# SmartRock_4-pin_EC_Breakout_v5.net
KiCad netlist of a schematic drawn in EAGLE
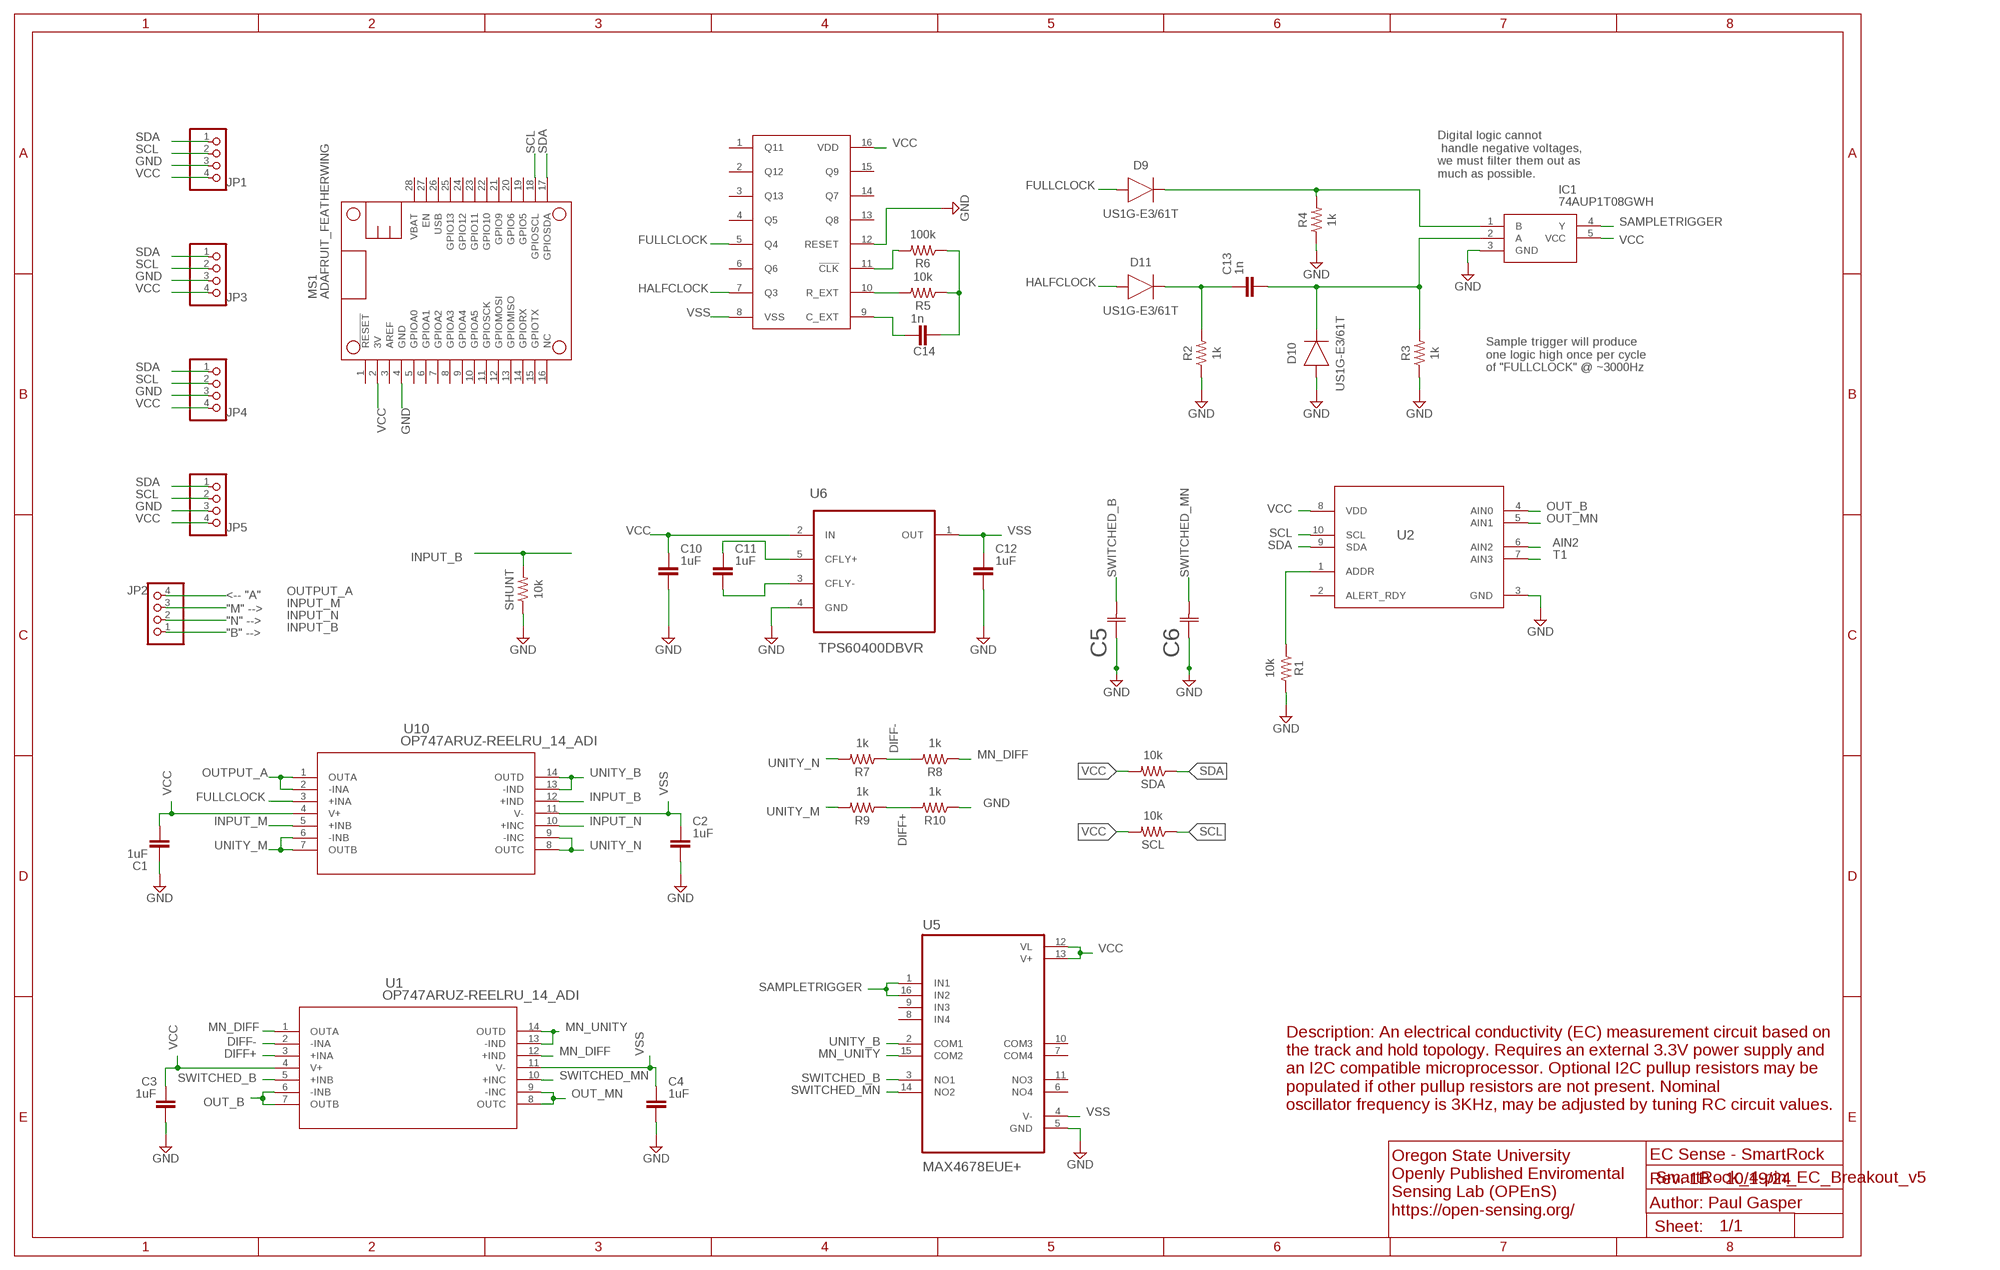
[diagram p0: schematic, sheet 1]

(export (version "E")
  (design (tool "Eeschema 10.0.6"))
  (components
    (comp (ref "C1")
      (value "1uF")
      (footprint "eagle-import:CAPC1005X60")
      (libsource (lib "eagle-import") (part "CCHIP-0402(1005-METRIC)_"))
    )
    (comp (ref "C2")
      (value "1uF")
      (footprint "eagle-import:CAPC1005X60")
      (libsource (lib "eagle-import") (part "CCHIP-0402(1005-METRIC)_"))
    )
    (comp (ref "C3")
      (value "1uF")
      (footprint "eagle-import:CAPC1005X60")
      (libsource (lib "eagle-import") (part "CCHIP-0402(1005-METRIC)_"))
    )
    (comp (ref "C4")
      (value "1uF")
      (footprint "eagle-import:CAPC1005X60")
      (libsource (lib "eagle-import") (part "CCHIP-0402(1005-METRIC)_"))
    )
    (comp (ref "C5")
      (value "865090640004CAP_WCAP-ASLU_04P0X05P5_WRE-L")
      (footprint "eagle-import:CAP_WCAP-ASLU_04P0X05P5_WRE-L")
      (fields
        (field (name "MANUFACTURER_PART_NUMBER") "865090640004")
        (field (name "COPYRIGHT") "Copyright (C) 2024 Ultra Librarian. All rights reserved.")
      )
      (libsource (lib "eagle-import") (part "865090640004CAP_WCAP-ASLU_04P0X05P5_WRE-L"))
    )
    (comp (ref "C6")
      (value "865090640004CAP_WCAP-ASLU_04P0X05P5_WRE-L")
      (footprint "eagle-import:CAP_WCAP-ASLU_04P0X05P5_WRE-L")
      (fields
        (field (name "MANUFACTURER_PART_NUMBER") "865090640004")
        (field (name "COPYRIGHT") "Copyright (C) 2024 Ultra Librarian. All rights reserved.")
      )
      (libsource (lib "eagle-import") (part "865090640004CAP_WCAP-ASLU_04P0X05P5_WRE-L"))
    )
    (comp (ref "C10")
      (value "1uF")
      (footprint "eagle-import:CAPC1005X60")
      (libsource (lib "eagle-import") (part "CCHIP-0402(1005-METRIC)_"))
    )
    (comp (ref "C11")
      (value "1uF")
      (footprint "eagle-import:CAPC1005X60")
      (libsource (lib "eagle-import") (part "CCHIP-0402(1005-METRIC)_"))
    )
    (comp (ref "C12")
      (value "1uF")
      (footprint "eagle-import:CAPC1005X60")
      (libsource (lib "eagle-import") (part "CCHIP-0402(1005-METRIC)_"))
    )
    (comp (ref "C13")
      (value "1n")
      (footprint "eagle-import:CAPC1005X60")
      (libsource (lib "eagle-import") (part "CCHIP-0402(1005-METRIC)_"))
    )
    (comp (ref "C14")
      (value "1n")
      (footprint "eagle-import:CAPC1005X60")
      (libsource (lib "eagle-import") (part "CCHIP-0402(1005-METRIC)_"))
    )
    (comp (ref "D9")
      (value "US1G-E3/61T")
      (footprint "eagle-import:DIOM5226X290N")
      (fields (field (name "MANUFACTURER") "Vishay Semiconductor Diodes Division"))
      (libsource (lib "eagle-import") (part "DIODE__SMAUS1G-E3/61T"))
    )
    (comp (ref "D10")
      (value "US1G-E3/61T")
      (footprint "eagle-import:DIOM5226X290N")
      (fields (field (name "MANUFACTURER") "Vishay Semiconductor Diodes Division"))
      (libsource (lib "eagle-import") (part "DIODE__SMAUS1G-E3/61T"))
    )
    (comp (ref "D11")
      (value "US1G-E3/61T")
      (footprint "eagle-import:DIOM5226X290N")
      (fields (field (name "MANUFACTURER") "Vishay Semiconductor Diodes Division"))
      (libsource (lib "eagle-import") (part "DIODE__SMAUS1G-E3/61T"))
    )
    (comp (ref "IC1")
      (value "74AUP1T08GWH")
      (footprint "eagle-import:SOT65P212X110-5N")
      (fields (field (name "MOUSER_PART_NUMBER") "771-74AUP1T08GWH"))
      (libsource (lib "eagle-import") (part "74AUP1T08GWH"))
    )
    (comp (ref "JP1")
      (value "PINHD-1X4")
      (footprint "eagle-import:1X04")
      (libsource (lib "eagle-import") (part "PINHD-1X4"))
    )
    (comp (ref "JP2")
      (value "PINHD-1X4")
      (footprint "eagle-import:1X04")
      (libsource (lib "eagle-import") (part "PINHD-1X4"))
    )
    (comp (ref "JP3")
      (value "PINHD-1X4")
      (footprint "eagle-import:1X04")
      (libsource (lib "eagle-import") (part "PINHD-1X4"))
    )
    (comp (ref "JP4")
      (value "PINHD-1X4")
      (footprint "eagle-import:1X04")
      (libsource (lib "eagle-import") (part "PINHD-1X4"))
    )
    (comp (ref "JP5")
      (value "PINHD-1X4")
      (footprint "eagle-import:1X04")
      (libsource (lib "eagle-import") (part "PINHD-1X4"))
    )
    (comp (ref "MS1")
      (value "ADAFRUIT_FEATHERWING")
      (footprint "eagle-import:ADAFRUIT_FEATHERWING")
      (libsource (lib "eagle-import") (part "ADAFRUIT_FEATHERWING"))
    )
    (comp (ref "R1")
      (value "10k")
      (footprint "eagle-import:RESC1005X40")
      (libsource (lib "eagle-import") (part "R-USCHIP-0402(1005-METRIC)_"))
    )
    (comp (ref "R2")
      (value "1k")
      (footprint "eagle-import:RESC1005X40")
      (libsource (lib "eagle-import") (part "R-USCHIP-0402(1005-METRIC)_"))
    )
    (comp (ref "R3")
      (value "1k")
      (footprint "eagle-import:RESC1005X40")
      (libsource (lib "eagle-import") (part "R-USCHIP-0402(1005-METRIC)_"))
    )
    (comp (ref "R4")
      (value "1k")
      (footprint "eagle-import:RESC1005X40")
      (libsource (lib "eagle-import") (part "R-USCHIP-0402(1005-METRIC)_"))
    )
    (comp (ref "R5")
      (value "10k")
      (footprint "eagle-import:RESC1005X40")
      (libsource (lib "eagle-import") (part "R-USCHIP-0402(1005-METRIC)_"))
    )
    (comp (ref "R6")
      (value "100k")
      (footprint "eagle-import:RESC1005X40")
      (libsource (lib "eagle-import") (part "R-USCHIP-0402(1005-METRIC)_"))
    )
    (comp (ref "R7")
      (value "1k")
      (footprint "eagle-import:RESC1005X40")
      (libsource (lib "eagle-import") (part "R-USCHIP-0402(1005-METRIC)_"))
    )
    (comp (ref "R8")
      (value "1k")
      (footprint "eagle-import:RESC1005X40")
      (libsource (lib "eagle-import") (part "R-USCHIP-0402(1005-METRIC)_"))
    )
    (comp (ref "R9")
      (value "1k")
      (footprint "eagle-import:RESC1005X40")
      (libsource (lib "eagle-import") (part "R-USCHIP-0402(1005-METRIC)_"))
    )
    (comp (ref "R10")
      (value "1k")
      (footprint "eagle-import:RESC1005X40")
      (libsource (lib "eagle-import") (part "R-USCHIP-0402(1005-METRIC)_"))
    )
    (comp (ref "SCL")
      (value "10k")
      (footprint "eagle-import:RESC1005X40")
      (libsource (lib "eagle-import") (part "R-USCHIP-0402(1005-METRIC)_"))
    )
    (comp (ref "SDA")
      (value "10k")
      (footprint "eagle-import:RESC1005X40")
      (libsource (lib "eagle-import") (part "R-USCHIP-0402(1005-METRIC)_"))
    )
    (comp (ref "SHUNT")
      (value "10k")
      (footprint "eagle-import:RESC1005X40")
      (libsource (lib "eagle-import") (part "R-USCHIP-0402(1005-METRIC)_"))
    )
    (comp (ref "U1")
      (value "OP747ARUZ-REELRU_14_ADI")
      (footprint "eagle-import:RU_14_ADI")
      (fields
        (field (name "MANUFACTURER_PART_NUMBER") "OP747ARUZ-REEL")
        (field (name "COPYRIGHT") "Copyright (C) 2024 Ultra Librarian. All rights reserved.")
      )
      (libsource (lib "eagle-import") (part "OP747ARUZ-REELRU_14_ADI"))
    )
    (comp (ref "U2")
      (value "ADS1115IDGSRDGS0010A_L")
      (footprint "eagle-import:DGS0010A_L")
      (fields
        (field (name "MANUFACTURER_PART_NUMBER") "ADS1115IDGSR")
        (field (name "COPYRIGHT") "Copyright (C) 2024 Ultra Librarian. All rights reserved.")
      )
      (libsource (lib "eagle-import") (part "ADS1115IDGSRDGS0010A_L"))
    )
    (comp (ref "U4")
      (value "CD4060BPWR")
      (footprint "eagle-import:CD4060BPWR")
      (libsource (lib "eagle-import") (part "CD4060BPWR"))
    )
    (comp (ref "U5")
      (value "MAX4678EUE+")
      (footprint "eagle-import:SOP65P640X110-16N")
      (libsource (lib "eagle-import") (part "MAX4678EUE+"))
    )
    (comp (ref "U6")
      (value "TPS60400DBVR")
      (footprint "eagle-import:SOT95P280X145-5N")
      (fields (field (name "MF") "Texas Instruments"))
      (libsource (lib "eagle-import") (part "TPS60400DBVR"))
    )
    (comp (ref "U10")
      (value "OP747ARUZ-REELRU_14_ADI")
      (footprint "eagle-import:RU_14_ADI")
      (fields
        (field (name "MANUFACTURER_PART_NUMBER") "OP747ARUZ-REEL")
        (field (name "COPYRIGHT") "Copyright (C) 2024 Ultra Librarian. All rights reserved.")
      )
      (libsource (lib "eagle-import") (part "OP747ARUZ-REELRU_14_ADI"))
    )
  )
  (nets
    (net (code "1") (name "/AIN2") (class "Default")
      (node (ref "U2") (pin "6") (pinfunction "AIN2_6") (pintype "input"))
    )
    (net (code "2") (name "/DIFF+") (class "Default")
      (node (ref "R10") (pin "2") (pinfunction "2_2") (pintype "passive"))
      (node (ref "R9") (pin "1") (pinfunction "1_1") (pintype "passive"))
      (node (ref "U1") (pin "3") (pinfunction "+INA_3") (pintype "passive"))
    )
    (net (code "3") (name "/DIFF-") (class "Default")
      (node (ref "R7") (pin "1") (pinfunction "1_1") (pintype "passive"))
      (node (ref "R8") (pin "2") (pinfunction "2_2") (pintype "passive"))
      (node (ref "U1") (pin "2") (pinfunction "-INA_2") (pintype "passive"))
    )
    (net (code "4") (name "/FULLCLOCK") (class "Default")
      (node (ref "D9") (pin "2") (pinfunction "A_2") (pintype "passive"))
      (node (ref "U10") (pin "3") (pinfunction "+INA_3") (pintype "passive"))
      (node (ref "U4") (pin "5") (pinfunction "Q4_5") (pintype "bidirectional"))
    )
    (net (code "5") (name "/HALFCLOCK") (class "Default")
      (node (ref "D11") (pin "2") (pinfunction "A_2") (pintype "passive"))
      (node (ref "U4") (pin "7") (pinfunction "Q3_7") (pintype "bidirectional"))
    )
    (net (code "6") (name "/INPUT_B") (class "Default")
      (node (ref "JP2") (pin "1") (pinfunction "1_1") (pintype "passive"))
      (node (ref "SHUNT") (pin "2") (pinfunction "2_2") (pintype "passive"))
      (node (ref "U10") (pin "12") (pinfunction "+IND_12") (pintype "passive"))
    )
    (net (code "7") (name "/INPUT_M") (class "Default")
      (node (ref "JP2") (pin "3") (pinfunction "3_3") (pintype "passive"))
      (node (ref "U10") (pin "5") (pinfunction "+INB_5") (pintype "passive"))
    )
    (net (code "8") (name "/INPUT_N") (class "Default")
      (node (ref "JP2") (pin "2") (pinfunction "2_2") (pintype "passive"))
      (node (ref "U10") (pin "10") (pinfunction "+INC_10") (pintype "passive"))
    )
    (net (code "9") (name "/MN_DIFF") (class "Default")
      (node (ref "R8") (pin "1") (pinfunction "1_1") (pintype "passive"))
      (node (ref "U1") (pin "1") (pinfunction "OUTA_1") (pintype "passive"))
      (node (ref "U1") (pin "12") (pinfunction "+IND_12") (pintype "passive"))
    )
    (net (code "10") (name "/MN_UNITY") (class "Default")
      (node (ref "U1") (pin "13") (pinfunction "-IND_13") (pintype "passive"))
      (node (ref "U1") (pin "14") (pinfunction "OUTD_14") (pintype "passive"))
      (node (ref "U5") (pin "15") (pinfunction "COM2_15") (pintype "bidirectional"))
    )
    (net (code "11") (name "/OUTPUT_A") (class "Default")
      (node (ref "JP2") (pin "4") (pinfunction "4_4") (pintype "passive"))
      (node (ref "U10") (pin "1") (pinfunction "OUTA_1") (pintype "passive"))
      (node (ref "U10") (pin "2") (pinfunction "-INA_2") (pintype "passive"))
    )
    (net (code "12") (name "/OUT_B") (class "Default")
      (node (ref "U1") (pin "6") (pinfunction "-INB_6") (pintype "passive"))
      (node (ref "U1") (pin "7") (pinfunction "OUTB_7") (pintype "passive"))
      (node (ref "U2") (pin "4") (pinfunction "AIN0_4") (pintype "input"))
    )
    (net (code "13") (name "/OUT_MN") (class "Default")
      (node (ref "U1") (pin "8") (pinfunction "OUTC_8") (pintype "passive"))
      (node (ref "U1") (pin "9") (pinfunction "-INC_9") (pintype "passive"))
      (node (ref "U2") (pin "5") (pinfunction "AIN1_5") (pintype "input"))
    )
    (net (code "14") (name "/SAMPLETRIGGER") (class "Default")
      (node (ref "IC1") (pin "4") (pinfunction "Y_4") (pintype "bidirectional"))
      (node (ref "U5") (pin "1") (pinfunction "IN1_1") (pintype "input"))
      (node (ref "U5") (pin "16") (pinfunction "IN2_16") (pintype "input"))
    )
    (net (code "15") (name "/SWITCHED_B") (class "Default")
      (node (ref "C5") (pin "2") (pinfunction "2_2") (pintype "passive"))
      (node (ref "U1") (pin "5") (pinfunction "+INB_5") (pintype "passive"))
      (node (ref "U5") (pin "3") (pinfunction "NO1_3") (pintype "bidirectional"))
    )
    (net (code "16") (name "/SWITCHED_MN") (class "Default")
      (node (ref "C6") (pin "2") (pinfunction "2_2") (pintype "passive"))
      (node (ref "U1") (pin "10") (pinfunction "+INC_10") (pintype "passive"))
      (node (ref "U5") (pin "14") (pinfunction "NO2_14") (pintype "bidirectional"))
    )
    (net (code "17") (name "/T1") (class "Default")
      (node (ref "U2") (pin "7") (pinfunction "AIN3_7") (pintype "input"))
    )
    (net (code "18") (name "/UNITY_B") (class "Default")
      (node (ref "U10") (pin "13") (pinfunction "-IND_13") (pintype "passive"))
      (node (ref "U10") (pin "14") (pinfunction "OUTD_14") (pintype "passive"))
      (node (ref "U5") (pin "2") (pinfunction "COM1_2") (pintype "bidirectional"))
    )
    (net (code "19") (name "/UNITY_M") (class "Default")
      (node (ref "R9") (pin "2") (pinfunction "2_2") (pintype "passive"))
      (node (ref "U10") (pin "6") (pinfunction "-INB_6") (pintype "passive"))
      (node (ref "U10") (pin "7") (pinfunction "OUTB_7") (pintype "passive"))
    )
    (net (code "20") (name "/UNITY_N") (class "Default")
      (node (ref "R7") (pin "2") (pinfunction "2_2") (pintype "passive"))
      (node (ref "U10") (pin "8") (pinfunction "OUTC_8") (pintype "passive"))
      (node (ref "U10") (pin "9") (pinfunction "-INC_9") (pintype "passive"))
    )
    (net (code "21") (name "/USB") (class "Default")
      (node (ref "MS1") (pin "26") (pinfunction "USB_26") (pintype "power_in"))
    )
    (net (code "22") (name "/VBAT") (class "Default")
      (node (ref "MS1") (pin "28") (pinfunction "VBAT_28") (pintype "power_in"))
    )
    (net (code "23") (name "/VSS") (class "Default")
      (node (ref "C12") (pin "1") (pinfunction "1_1") (pintype "passive"))
      (node (ref "C2") (pin "1") (pinfunction "1_1") (pintype "passive"))
      (node (ref "C4") (pin "1") (pinfunction "1_1") (pintype "passive"))
      (node (ref "U1") (pin "11") (pinfunction "V-_11") (pintype "power_in"))
      (node (ref "U10") (pin "11") (pinfunction "V-_11") (pintype "power_in"))
      (node (ref "U4") (pin "8") (pinfunction "VSS_8") (pintype "bidirectional"))
      (node (ref "U5") (pin "4") (pinfunction "V-_4") (pintype "power_in"))
      (node (ref "U6") (pin "1") (pinfunction "OUT_1") (pintype "output"))
    )
    (net (code "24") (name "GND") (class "Default")
      (node (ref "C1") (pin "1") (pinfunction "1_1") (pintype "passive"))
      (node (ref "C10") (pin "2") (pinfunction "2_2") (pintype "passive"))
      (node (ref "C12") (pin "2") (pinfunction "2_2") (pintype "passive"))
      (node (ref "C2") (pin "2") (pinfunction "2_2") (pintype "passive"))
      (node (ref "C3") (pin "2") (pinfunction "2_2") (pintype "passive"))
      (node (ref "C4") (pin "2") (pinfunction "2_2") (pintype "passive"))
      (node (ref "C5") (pin "1") (pinfunction "1_1") (pintype "passive"))
      (node (ref "C6") (pin "1") (pinfunction "1_1") (pintype "passive"))
      (node (ref "D10") (pin "2") (pinfunction "A_2") (pintype "passive"))
      (node (ref "IC1") (pin "3") (pinfunction "GND_3") (pintype "bidirectional"))
      (node (ref "JP1") (pin "3") (pinfunction "3_3") (pintype "passive"))
      (node (ref "JP3") (pin "3") (pinfunction "3_3") (pintype "passive"))
      (node (ref "JP4") (pin "3") (pinfunction "3_3") (pintype "passive"))
      (node (ref "JP5") (pin "3") (pinfunction "3_3") (pintype "passive"))
      (node (ref "MS1") (pin "4") (pinfunction "GND_4") (pintype "power_in"))
      (node (ref "R1") (pin "2") (pinfunction "2_2") (pintype "passive"))
      (node (ref "R10") (pin "1") (pinfunction "1_1") (pintype "passive"))
      (node (ref "R2") (pin "1") (pinfunction "1_1") (pintype "passive"))
      (node (ref "R3") (pin "1") (pinfunction "1_1") (pintype "passive"))
      (node (ref "R4") (pin "1") (pinfunction "1_1") (pintype "passive"))
      (node (ref "SHUNT") (pin "1") (pinfunction "1_1") (pintype "passive"))
      (node (ref "U2") (pin "3") (pinfunction "GND_3") (pintype "power_in"))
      (node (ref "U4") (pin "12") (pinfunction "RESET_12") (pintype "bidirectional"))
      (node (ref "U5") (pin "5") (pinfunction "GND_5") (pintype "power_in"))
      (node (ref "U6") (pin "4") (pinfunction "GND_4") (pintype "passive"))
    )
    (net (code "25") (name "Net-(C14-Pad2)") (class "Default")
      (node (ref "C14") (pin "2") (pinfunction "2_2") (pintype "passive"))
      (node (ref "R5") (pin "1") (pinfunction "1_1") (pintype "passive"))
      (node (ref "R6") (pin "1") (pinfunction "1_1") (pintype "passive"))
    )
    (net (code "26") (name "Net-(D9-C)") (class "Default")
      (node (ref "D9") (pin "1") (pinfunction "C_1") (pintype "passive"))
      (node (ref "IC1") (pin "1") (pinfunction "B_1") (pintype "bidirectional"))
      (node (ref "R4") (pin "2") (pinfunction "2_2") (pintype "passive"))
    )
    (net (code "27") (name "Net-(D10-C)") (class "Default")
      (node (ref "C13") (pin "2") (pinfunction "2_2") (pintype "passive"))
      (node (ref "D10") (pin "1") (pinfunction "C_1") (pintype "passive"))
      (node (ref "IC1") (pin "2") (pinfunction "A_2") (pintype "bidirectional"))
      (node (ref "R3") (pin "2") (pinfunction "2_2") (pintype "passive"))
    )
    (net (code "28") (name "Net-(D11-C)") (class "Default")
      (node (ref "C13") (pin "1") (pinfunction "1_1") (pintype "passive"))
      (node (ref "D11") (pin "1") (pinfunction "C_1") (pintype "passive"))
      (node (ref "R2") (pin "2") (pinfunction "2_2") (pintype "passive"))
    )
    (net (code "29") (name "Net-(U2-ADDR)") (class "Default")
      (node (ref "R1") (pin "1") (pinfunction "1_1") (pintype "passive"))
      (node (ref "U2") (pin "1") (pinfunction "ADDR_1") (pintype "input"))
    )
    (net (code "30") (name "Net-(U4-C_EXT)") (class "Default")
      (node (ref "C14") (pin "1") (pinfunction "1_1") (pintype "passive"))
      (node (ref "U4") (pin "9") (pinfunction "C_EXT_9") (pintype "bidirectional"))
    )
    (net (code "31") (name "Net-(U4-R_EXT)") (class "Default")
      (node (ref "R5") (pin "2") (pinfunction "2_2") (pintype "passive"))
      (node (ref "U4") (pin "10") (pinfunction "R_EXT_10") (pintype "bidirectional"))
    )
    (net (code "32") (name "Net-(U4-~{CLK})") (class "Default")
      (node (ref "R6") (pin "2") (pinfunction "2_2") (pintype "passive"))
      (node (ref "U4") (pin "11") (pinfunction "~{CLK}_11") (pintype "bidirectional"))
    )
    (net (code "33") (name "Net-(U6-CFLY+)") (class "Default")
      (node (ref "C11") (pin "1") (pinfunction "1_1") (pintype "passive"))
      (node (ref "U6") (pin "5") (pinfunction "CFLY+_5") (pintype "input"))
    )
    (net (code "34") (name "Net-(U6-CFLY-)") (class "Default")
      (node (ref "C11") (pin "2") (pinfunction "2_2") (pintype "passive"))
      (node (ref "U6") (pin "3") (pinfunction "CFLY-_3") (pintype "input"))
    )
    (net (code "35") (name "SCL") (class "Default")
      (node (ref "JP1") (pin "2") (pinfunction "2_2") (pintype "passive"))
      (node (ref "JP3") (pin "2") (pinfunction "2_2") (pintype "passive"))
      (node (ref "JP4") (pin "2") (pinfunction "2_2") (pintype "passive"))
      (node (ref "JP5") (pin "2") (pinfunction "2_2") (pintype "passive"))
      (node (ref "MS1") (pin "18") (pinfunction "GPIOSCL_18") (pintype "bidirectional"))
      (node (ref "SCL") (pin "1") (pinfunction "1_1") (pintype "passive"))
      (node (ref "U2") (pin "10") (pinfunction "SCL_10") (pintype "input"))
    )
    (net (code "36") (name "SDA") (class "Default")
      (node (ref "JP1") (pin "1") (pinfunction "1_1") (pintype "passive"))
      (node (ref "JP3") (pin "1") (pinfunction "1_1") (pintype "passive"))
      (node (ref "JP4") (pin "1") (pinfunction "1_1") (pintype "passive"))
      (node (ref "JP5") (pin "1") (pinfunction "1_1") (pintype "passive"))
      (node (ref "MS1") (pin "17") (pinfunction "GPIOSDA_17") (pintype "bidirectional"))
      (node (ref "SDA") (pin "1") (pinfunction "1_1") (pintype "passive"))
      (node (ref "U2") (pin "9") (pinfunction "SDA_9") (pintype "bidirectional"))
    )
    (net (code "37") (name "VCC") (class "Default")
      (node (ref "C1") (pin "2") (pinfunction "2_2") (pintype "passive"))
      (node (ref "C10") (pin "1") (pinfunction "1_1") (pintype "passive"))
      (node (ref "C3") (pin "1") (pinfunction "1_1") (pintype "passive"))
      (node (ref "IC1") (pin "5") (pinfunction "VCC_5") (pintype "bidirectional"))
      (node (ref "JP1") (pin "4") (pinfunction "4_4") (pintype "passive"))
      (node (ref "JP3") (pin "4") (pinfunction "4_4") (pintype "passive"))
      (node (ref "JP4") (pin "4") (pinfunction "4_4") (pintype "passive"))
      (node (ref "JP5") (pin "4") (pinfunction "4_4") (pintype "passive"))
      (node (ref "MS1") (pin "2") (pinfunction "3V_2") (pintype "power_in"))
      (node (ref "SCL") (pin "2") (pinfunction "2_2") (pintype "passive"))
      (node (ref "SDA") (pin "2") (pinfunction "2_2") (pintype "passive"))
      (node (ref "U1") (pin "4") (pinfunction "V+_4") (pintype "power_in"))
      (node (ref "U10") (pin "4") (pinfunction "V+_4") (pintype "power_in"))
      (node (ref "U2") (pin "8") (pinfunction "VDD_8") (pintype "power_in"))
      (node (ref "U4") (pin "16") (pinfunction "VDD_16") (pintype "bidirectional"))
      (node (ref "U5") (pin "12") (pinfunction "VL_12") (pintype "power_in"))
      (node (ref "U5") (pin "13") (pinfunction "V+_13") (pintype "power_in"))
      (node (ref "U6") (pin "2") (pinfunction "IN_2") (pintype "power_in"))
    )
    (net (code "38") (name "unconnected-(MS1-AREF-Pad3)") (class "Default")
      (node (ref "MS1") (pin "3") (pinfunction "AREF_3") (pintype "passive"))
    )
    (net (code "39") (name "unconnected-(MS1-EN-Pad27)") (class "Default")
      (node (ref "MS1") (pin "27") (pinfunction "EN_27") (pintype "passive"))
    )
    (net (code "40") (name "unconnected-(MS1-GPIO5-Pad19)") (class "Default")
      (node (ref "MS1") (pin "19") (pinfunction "GPIO5_19") (pintype "bidirectional"))
    )
    (net (code "41") (name "unconnected-(MS1-GPIO6-Pad20)") (class "Default")
      (node (ref "MS1") (pin "20") (pinfunction "GPIO6_20") (pintype "bidirectional"))
    )
    (net (code "42") (name "unconnected-(MS1-GPIO9-Pad21)") (class "Default")
      (node (ref "MS1") (pin "21") (pinfunction "GPIO9_21") (pintype "bidirectional"))
    )
    (net (code "43") (name "unconnected-(MS1-GPIO10-Pad22)") (class "Default")
      (node (ref "MS1") (pin "22") (pinfunction "GPIO10_22") (pintype "bidirectional"))
    )
    (net (code "44") (name "unconnected-(MS1-GPIO11-Pad23)") (class "Default")
      (node (ref "MS1") (pin "23") (pinfunction "GPIO11_23") (pintype "bidirectional"))
    )
    (net (code "45") (name "unconnected-(MS1-GPIO12-Pad24)") (class "Default")
      (node (ref "MS1") (pin "24") (pinfunction "GPIO12_24") (pintype "bidirectional"))
    )
    (net (code "46") (name "unconnected-(MS1-GPIO13-Pad25)") (class "Default")
      (node (ref "MS1") (pin "25") (pinfunction "GPIO13_25") (pintype "bidirectional"))
    )
    (net (code "47") (name "unconnected-(MS1-GPIOA0-Pad5)") (class "Default")
      (node (ref "MS1") (pin "5") (pinfunction "GPIOA0_5") (pintype "bidirectional"))
    )
    (net (code "48") (name "unconnected-(MS1-GPIOA1-Pad6)") (class "Default")
      (node (ref "MS1") (pin "6") (pinfunction "GPIOA1_6") (pintype "bidirectional"))
    )
    (net (code "49") (name "unconnected-(MS1-GPIOA2-Pad7)") (class "Default")
      (node (ref "MS1") (pin "7") (pinfunction "GPIOA2_7") (pintype "bidirectional"))
    )
    (net (code "50") (name "unconnected-(MS1-GPIOA3-Pad8)") (class "Default")
      (node (ref "MS1") (pin "8") (pinfunction "GPIOA3_8") (pintype "bidirectional"))
    )
    (net (code "51") (name "unconnected-(MS1-GPIOA4-Pad9)") (class "Default")
      (node (ref "MS1") (pin "9") (pinfunction "GPIOA4_9") (pintype "bidirectional"))
    )
    (net (code "52") (name "unconnected-(MS1-GPIOA5-Pad10)") (class "Default")
      (node (ref "MS1") (pin "10") (pinfunction "GPIOA5_10") (pintype "bidirectional"))
    )
    (net (code "53") (name "unconnected-(MS1-GPIOMISO-Pad13)") (class "Default")
      (node (ref "MS1") (pin "13") (pinfunction "GPIOMISO_13") (pintype "bidirectional"))
    )
    (net (code "54") (name "unconnected-(MS1-GPIOMOSI-Pad12)") (class "Default")
      (node (ref "MS1") (pin "12") (pinfunction "GPIOMOSI_12") (pintype "bidirectional"))
    )
    (net (code "55") (name "unconnected-(MS1-GPIORX-Pad14)") (class "Default")
      (node (ref "MS1") (pin "14") (pinfunction "GPIORX_14") (pintype "bidirectional"))
    )
    (net (code "56") (name "unconnected-(MS1-GPIOSCK-Pad11)") (class "Default")
      (node (ref "MS1") (pin "11") (pinfunction "GPIOSCK_11") (pintype "bidirectional"))
    )
    (net (code "57") (name "unconnected-(MS1-GPIOTX-Pad15)") (class "Default")
      (node (ref "MS1") (pin "15") (pinfunction "GPIOTX_15") (pintype "bidirectional"))
    )
    (net (code "58") (name "unconnected-(MS1-NC-Pad16)") (class "Default")
      (node (ref "MS1") (pin "16") (pinfunction "NC_16") (pintype "passive"))
    )
    (net (code "59") (name "unconnected-(MS1-~{RESET}-Pad1)") (class "Default")
      (node (ref "MS1") (pin "1") (pinfunction "~{RESET}_1") (pintype "input"))
    )
    (net (code "60") (name "unconnected-(U2-ALERT_RDY-Pad2)") (class "Default")
      (node (ref "U2") (pin "2") (pinfunction "ALERT_RDY_2") (pintype "output"))
    )
    (net (code "61") (name "unconnected-(U4-Q5-Pad4)") (class "Default")
      (node (ref "U4") (pin "4") (pinfunction "Q5_4") (pintype "bidirectional"))
    )
    (net (code "62") (name "unconnected-(U4-Q6-Pad6)") (class "Default")
      (node (ref "U4") (pin "6") (pinfunction "Q6_6") (pintype "bidirectional"))
    )
    (net (code "63") (name "unconnected-(U4-Q7-Pad14)") (class "Default")
      (node (ref "U4") (pin "14") (pinfunction "Q7_14") (pintype "bidirectional"))
    )
    (net (code "64") (name "unconnected-(U4-Q8-Pad13)") (class "Default")
      (node (ref "U4") (pin "13") (pinfunction "Q8_13") (pintype "bidirectional"))
    )
    (net (code "65") (name "unconnected-(U4-Q9-Pad15)") (class "Default")
      (node (ref "U4") (pin "15") (pinfunction "Q9_15") (pintype "bidirectional"))
    )
    (net (code "66") (name "unconnected-(U4-Q11-Pad1)") (class "Default")
      (node (ref "U4") (pin "1") (pinfunction "Q11_1") (pintype "bidirectional"))
    )
    (net (code "67") (name "unconnected-(U4-Q12-Pad2)") (class "Default")
      (node (ref "U4") (pin "2") (pinfunction "Q12_2") (pintype "bidirectional"))
    )
    (net (code "68") (name "unconnected-(U4-Q13-Pad3)") (class "Default")
      (node (ref "U4") (pin "3") (pinfunction "Q13_3") (pintype "bidirectional"))
    )
    (net (code "69") (name "unconnected-(U5-COM3-Pad10)") (class "Default")
      (node (ref "U5") (pin "10") (pinfunction "COM3_10") (pintype "bidirectional"))
    )
    (net (code "70") (name "unconnected-(U5-COM4-Pad7)") (class "Default")
      (node (ref "U5") (pin "7") (pinfunction "COM4_7") (pintype "bidirectional"))
    )
    (net (code "71") (name "unconnected-(U5-IN3-Pad9)") (class "Default")
      (node (ref "U5") (pin "9") (pinfunction "IN3_9") (pintype "input"))
    )
    (net (code "72") (name "unconnected-(U5-IN4-Pad8)") (class "Default")
      (node (ref "U5") (pin "8") (pinfunction "IN4_8") (pintype "input"))
    )
    (net (code "73") (name "unconnected-(U5-NO3-Pad11)") (class "Default")
      (node (ref "U5") (pin "11") (pinfunction "NO3_11") (pintype "bidirectional"))
    )
    (net (code "74") (name "unconnected-(U5-NO4-Pad6)") (class "Default")
      (node (ref "U5") (pin "6") (pinfunction "NO4_6") (pintype "bidirectional"))
    )
  )
)
